# xmas_tree_proto_v1.net
KiCad netlist of a schematic drawn in EAGLE
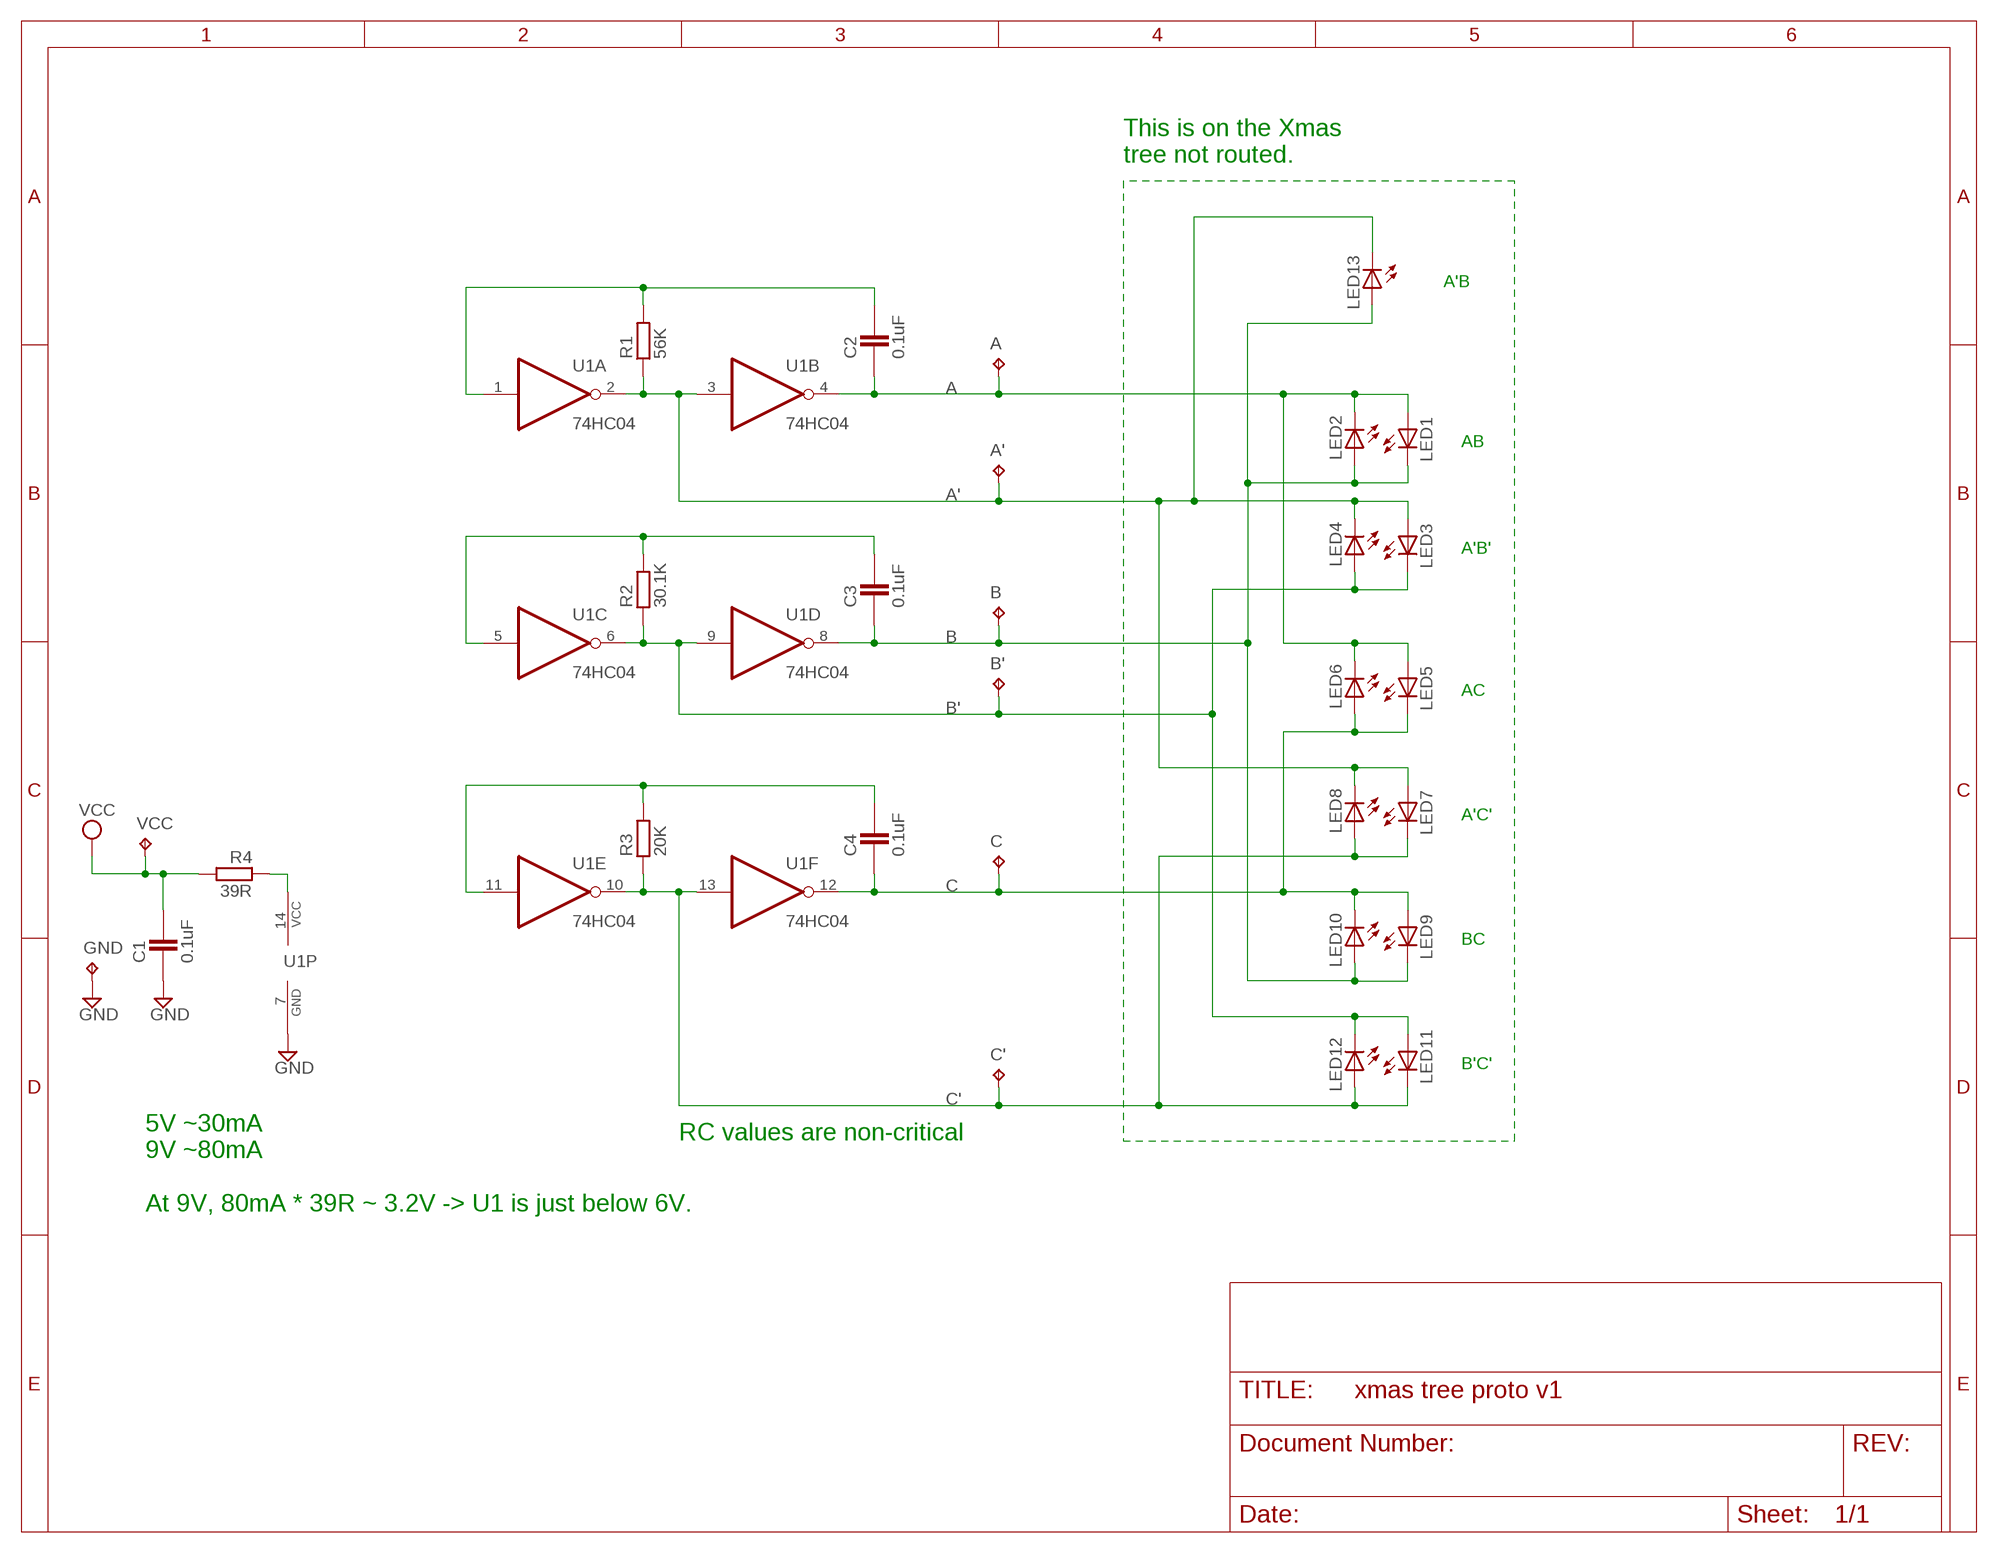
[diagram p0: schematic, sheet 1]

(export (version "E")
  (design (tool "Eeschema 10.0.6"))
  (components
    (comp (ref "A")
      (value "TPTP10SQ")
      (footprint "eagle-import:TP10SQ")
      (libsource (lib "eagle-import") (part "TPTP10SQ"))
    )
    (comp (ref "A'")
      (value "TPTP10SQ")
      (footprint "eagle-import:TP10SQ")
      (libsource (lib "eagle-import") (part "TPTP10SQ"))
    )
    (comp (ref "B")
      (value "TPTP10SQ")
      (footprint "eagle-import:TP10SQ")
      (libsource (lib "eagle-import") (part "TPTP10SQ"))
    )
    (comp (ref "B'")
      (value "TPTP10SQ")
      (footprint "eagle-import:TP10SQ")
      (libsource (lib "eagle-import") (part "TPTP10SQ"))
    )
    (comp (ref "C")
      (value "TPTP10SQ")
      (footprint "eagle-import:TP10SQ")
      (libsource (lib "eagle-import") (part "TPTP10SQ"))
    )
    (comp (ref "C'")
      (value "TPTP10SQ")
      (footprint "eagle-import:TP10SQ")
      (libsource (lib "eagle-import") (part "TPTP10SQ"))
    )
    (comp (ref "C1")
      (value "0.1uF")
      (footprint "eagle-import:CAP2012X70N")
      (libsource (lib "eagle-import") (part "CAPACITOR_0805N"))
    )
    (comp (ref "C2")
      (value "0.1uF")
      (footprint "eagle-import:CAPC1608X92N")
      (libsource (lib "eagle-import") (part "CAPACITOR_0603"))
    )
    (comp (ref "C3")
      (value "0.1uF")
      (footprint "eagle-import:CAPC1608X92N")
      (libsource (lib "eagle-import") (part "CAPACITOR_0603"))
    )
    (comp (ref "C4")
      (value "0.1uF")
      (footprint "eagle-import:CAPC1608X92N")
      (libsource (lib "eagle-import") (part "CAPACITOR_0603"))
    )
    (comp (ref "GND")
      (value "TPTP20SQ")
      (footprint "eagle-import:TP20SQ")
      (libsource (lib "eagle-import") (part "TPTP20SQ"))
    )
    (comp (ref "LED1")
      (value "LED3MM")
      (footprint "eagle-import:LED3MM")
      (libsource (lib "eagle-import") (part "LED3MM"))
    )
    (comp (ref "LED2")
      (value "LED3MM")
      (footprint "eagle-import:LED3MM")
      (libsource (lib "eagle-import") (part "LED3MM"))
    )
    (comp (ref "LED3")
      (value "LED3MM")
      (footprint "eagle-import:LED3MM")
      (libsource (lib "eagle-import") (part "LED3MM"))
    )
    (comp (ref "LED4")
      (value "LED3MM")
      (footprint "eagle-import:LED3MM")
      (libsource (lib "eagle-import") (part "LED3MM"))
    )
    (comp (ref "LED5")
      (value "LED3MM")
      (footprint "eagle-import:LED3MM")
      (libsource (lib "eagle-import") (part "LED3MM"))
    )
    (comp (ref "LED6")
      (value "LED3MM")
      (footprint "eagle-import:LED3MM")
      (libsource (lib "eagle-import") (part "LED3MM"))
    )
    (comp (ref "LED7")
      (value "LED3MM")
      (footprint "eagle-import:LED3MM")
      (libsource (lib "eagle-import") (part "LED3MM"))
    )
    (comp (ref "LED8")
      (value "LED3MM")
      (footprint "eagle-import:LED3MM")
      (libsource (lib "eagle-import") (part "LED3MM"))
    )
    (comp (ref "LED9")
      (value "LED3MM")
      (footprint "eagle-import:LED3MM")
      (libsource (lib "eagle-import") (part "LED3MM"))
    )
    (comp (ref "LED10")
      (value "LED3MM")
      (footprint "eagle-import:LED3MM")
      (libsource (lib "eagle-import") (part "LED3MM"))
    )
    (comp (ref "LED11")
      (value "LED3MM")
      (footprint "eagle-import:LED3MM")
      (libsource (lib "eagle-import") (part "LED3MM"))
    )
    (comp (ref "LED12")
      (value "LED3MM")
      (footprint "eagle-import:LED3MM")
      (libsource (lib "eagle-import") (part "LED3MM"))
    )
    (comp (ref "LED13")
      (value "LED3MM")
      (footprint "eagle-import:LED3MM")
      (libsource (lib "eagle-import") (part "LED3MM"))
    )
    (comp (ref "R1")
      (value "56K")
      (footprint "eagle-import:RESC1608X55N")
      (libsource (lib "eagle-import") (part "RESISTOR_0603"))
    )
    (comp (ref "R2")
      (value "30.1K")
      (footprint "eagle-import:RESC1608X55N")
      (libsource (lib "eagle-import") (part "RESISTOR_0603"))
    )
    (comp (ref "R3")
      (value "20K")
      (footprint "eagle-import:RESC1608X55N")
      (libsource (lib "eagle-import") (part "RESISTOR_0603"))
    )
    (comp (ref "R4")
      (value "39R")
      (footprint "eagle-import:RESC1608X55N")
      (libsource (lib "eagle-import") (part "RESISTOR_0603"))
    )
    (comp (ref "U1")
      (value "74HC04")
      (footprint "eagle-import:SO14")
      (libsource (lib "eagle-import") (part "7404DAS"))
    )
    (comp (ref "VCC")
      (value "TPTP20SQ")
      (footprint "eagle-import:TP20SQ")
      (libsource (lib "eagle-import") (part "TPTP20SQ"))
    )
  )
  (nets
    (net (code "1") (name "/A") (class "Default")
      (node (ref "A") (pin "TP") (pinfunction "TP_TP") (pintype "input"))
      (node (ref "C2") (pin "1") (pinfunction "1_1") (pintype "passive"))
      (node (ref "LED1") (pin "A") (pinfunction "A_A") (pintype "passive"))
      (node (ref "LED2") (pin "K") (pinfunction "C_K") (pintype "passive"))
      (node (ref "LED5") (pin "A") (pinfunction "A_A") (pintype "passive"))
      (node (ref "LED6") (pin "K") (pinfunction "C_K") (pintype "passive"))
      (node (ref "U1") (pin "4") (pinfunction "O_4") (pintype "output"))
    )
    (net (code "2") (name "/A'") (class "Default")
      (node (ref "A'") (pin "TP") (pinfunction "TP_TP") (pintype "input"))
      (node (ref "LED13") (pin "K") (pinfunction "C_K") (pintype "passive"))
      (node (ref "LED3") (pin "A") (pinfunction "A_A") (pintype "passive"))
      (node (ref "LED4") (pin "K") (pinfunction "C_K") (pintype "passive"))
      (node (ref "LED7") (pin "A") (pinfunction "A_A") (pintype "passive"))
      (node (ref "LED8") (pin "K") (pinfunction "C_K") (pintype "passive"))
      (node (ref "R1") (pin "1") (pinfunction "1_1") (pintype "passive"))
      (node (ref "U1") (pin "2") (pinfunction "O_2") (pintype "output"))
      (node (ref "U1") (pin "3") (pinfunction "I_3") (pintype "input"))
    )
    (net (code "3") (name "/B") (class "Default")
      (node (ref "B") (pin "TP") (pinfunction "TP_TP") (pintype "input"))
      (node (ref "C3") (pin "1") (pinfunction "1_1") (pintype "passive"))
      (node (ref "LED1") (pin "K") (pinfunction "C_K") (pintype "passive"))
      (node (ref "LED10") (pin "A") (pinfunction "A_A") (pintype "passive"))
      (node (ref "LED13") (pin "A") (pinfunction "A_A") (pintype "passive"))
      (node (ref "LED2") (pin "A") (pinfunction "A_A") (pintype "passive"))
      (node (ref "LED9") (pin "K") (pinfunction "C_K") (pintype "passive"))
      (node (ref "U1") (pin "8") (pinfunction "O_8") (pintype "output"))
    )
    (net (code "4") (name "/B'") (class "Default")
      (node (ref "B'") (pin "TP") (pinfunction "TP_TP") (pintype "input"))
      (node (ref "LED11") (pin "A") (pinfunction "A_A") (pintype "passive"))
      (node (ref "LED12") (pin "K") (pinfunction "C_K") (pintype "passive"))
      (node (ref "LED3") (pin "K") (pinfunction "C_K") (pintype "passive"))
      (node (ref "LED4") (pin "A") (pinfunction "A_A") (pintype "passive"))
      (node (ref "R2") (pin "1") (pinfunction "1_1") (pintype "passive"))
      (node (ref "U1") (pin "6") (pinfunction "O_6") (pintype "output"))
      (node (ref "U1") (pin "9") (pinfunction "I_9") (pintype "input"))
    )
    (net (code "5") (name "/C") (class "Default")
      (node (ref "C") (pin "TP") (pinfunction "TP_TP") (pintype "input"))
      (node (ref "C4") (pin "1") (pinfunction "1_1") (pintype "passive"))
      (node (ref "LED10") (pin "K") (pinfunction "C_K") (pintype "passive"))
      (node (ref "LED5") (pin "K") (pinfunction "C_K") (pintype "passive"))
      (node (ref "LED6") (pin "A") (pinfunction "A_A") (pintype "passive"))
      (node (ref "LED9") (pin "A") (pinfunction "A_A") (pintype "passive"))
      (node (ref "U1") (pin "12") (pinfunction "O_12") (pintype "output"))
    )
    (net (code "6") (name "/C'") (class "Default")
      (node (ref "C'") (pin "TP") (pinfunction "TP_TP") (pintype "input"))
      (node (ref "LED11") (pin "K") (pinfunction "C_K") (pintype "passive"))
      (node (ref "LED12") (pin "A") (pinfunction "A_A") (pintype "passive"))
      (node (ref "LED7") (pin "K") (pinfunction "C_K") (pintype "passive"))
      (node (ref "LED8") (pin "A") (pinfunction "A_A") (pintype "passive"))
      (node (ref "R3") (pin "1") (pinfunction "1_1") (pintype "passive"))
      (node (ref "U1") (pin "10") (pinfunction "O_10") (pintype "output"))
      (node (ref "U1") (pin "13") (pinfunction "I_13") (pintype "input"))
    )
    (net (code "7") (name "GND") (class "Default")
      (node (ref "C1") (pin "1") (pinfunction "1_1") (pintype "passive"))
      (node (ref "GND") (pin "TP") (pinfunction "TP_TP") (pintype "input"))
      (node (ref "U1") (pin "7") (pinfunction "GND_7") (pintype "power_in"))
    )
    (net (code "8") (name "Net-(U1A-I)") (class "Default")
      (node (ref "C2") (pin "2") (pinfunction "2_2") (pintype "passive"))
      (node (ref "R1") (pin "2") (pinfunction "2_2") (pintype "passive"))
      (node (ref "U1") (pin "1") (pinfunction "I_1") (pintype "input"))
    )
    (net (code "9") (name "Net-(U1C-I)") (class "Default")
      (node (ref "C3") (pin "2") (pinfunction "2_2") (pintype "passive"))
      (node (ref "R2") (pin "2") (pinfunction "2_2") (pintype "passive"))
      (node (ref "U1") (pin "5") (pinfunction "I_5") (pintype "input"))
    )
    (net (code "10") (name "Net-(U1E-I)") (class "Default")
      (node (ref "C4") (pin "2") (pinfunction "2_2") (pintype "passive"))
      (node (ref "R3") (pin "2") (pinfunction "2_2") (pintype "passive"))
      (node (ref "U1") (pin "11") (pinfunction "I_11") (pintype "input"))
    )
    (net (code "11") (name "Net-(U1G-VCC)") (class "Default")
      (node (ref "R4") (pin "1") (pinfunction "1_1") (pintype "passive"))
      (node (ref "U1") (pin "14") (pinfunction "VCC_14") (pintype "power_in"))
    )
    (net (code "12") (name "VCC") (class "Default")
      (node (ref "C1") (pin "2") (pinfunction "2_2") (pintype "passive"))
      (node (ref "R4") (pin "2") (pinfunction "2_2") (pintype "passive"))
      (node (ref "VCC") (pin "TP") (pinfunction "TP_TP") (pintype "input"))
    )
  )
)
